# M5_Camera.net
KiCad netlist of a schematic drawn in Altium Designer
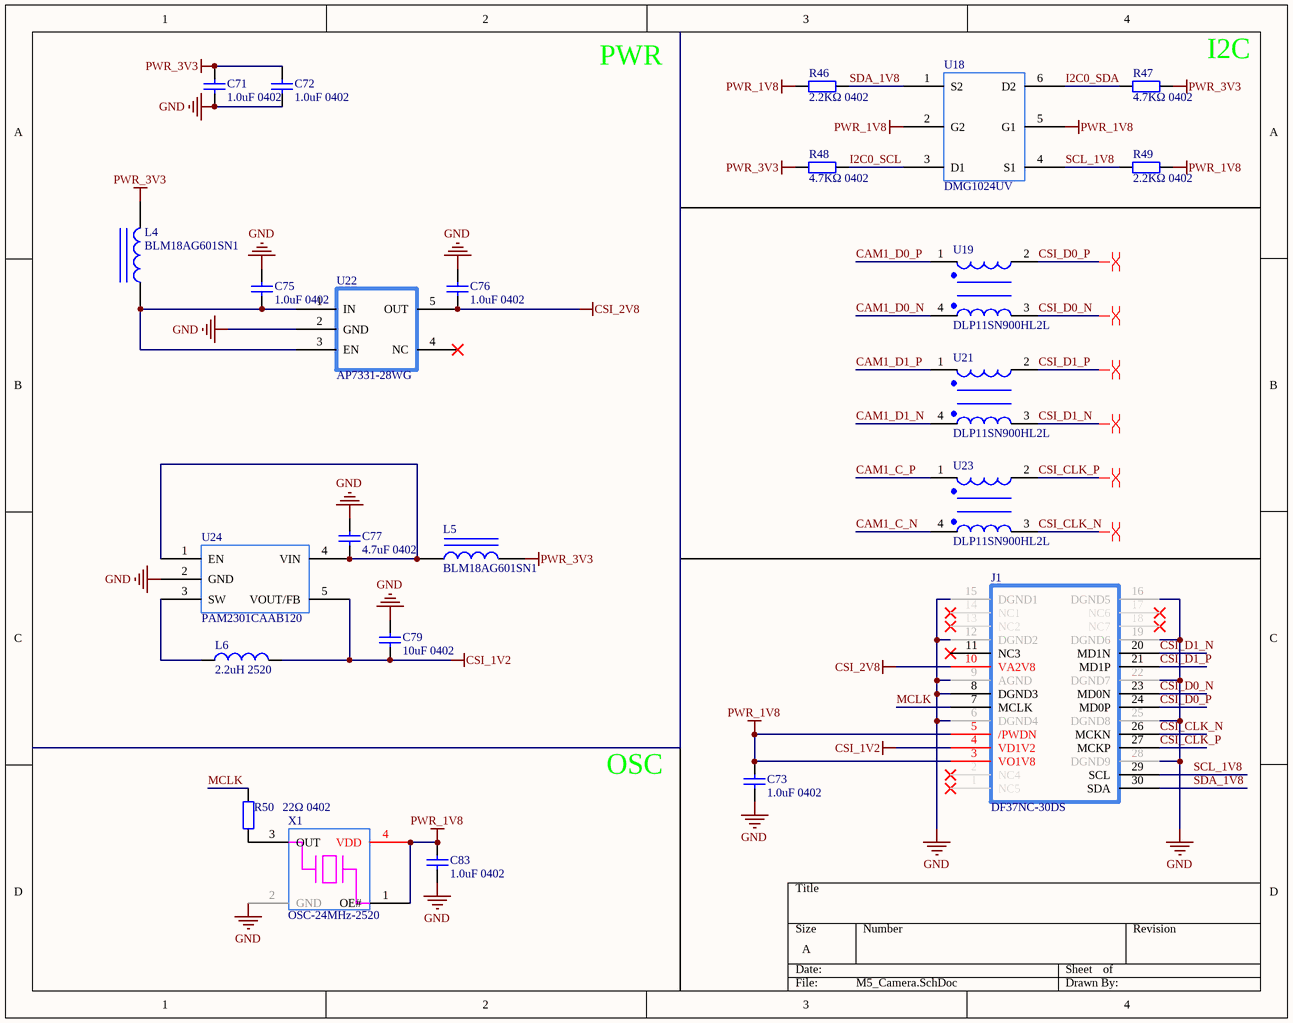
[diagram p0: M5_Camera.SchDoc]

(export (version "E")
  (design (tool "Eeschema 10.0.6"))
  (components
    (comp (ref "C71")
      (value "1.0uF 0402")
      (footprint "0402_C")
      (description "贴片电容")
      (libsource (lib "Miscellaneous Devices LC") (part "0402 1.0uF (105) 10% 25V"))
    )
    (comp (ref "C72")
      (value "1.0uF 0402")
      (footprint "0402_C")
      (description "贴片电容")
      (libsource (lib "Miscellaneous Devices LC") (part "0402 1.0uF (105) 10% 25V"))
    )
    (comp (ref "C73")
      (value "1.0uF 0402")
      (footprint "0402_C")
      (description "贴片电容")
      (libsource (lib "Miscellaneous Devices LC") (part "0402 1.0uF (105) 10% 25V"))
    )
    (comp (ref "C75")
      (value "1.0uF 0402")
      (footprint "0402_C")
      (description "贴片电容")
      (libsource (lib "Miscellaneous Devices LC") (part "0402 1.0uF (105) 10% 25V"))
    )
    (comp (ref "C76")
      (value "1.0uF 0402")
      (footprint "0402_C")
      (description "贴片电容")
      (libsource (lib "Miscellaneous Devices LC") (part "0402 1.0uF (105) 10% 25V"))
    )
    (comp (ref "C77")
      (value "4.7uF 0402")
      (footprint "0402_C")
      (description "贴片电容")
      (libsource (lib "Miscellaneous Devices LC") (part "0402 4.7uF (475) 20% 10V"))
    )
    (comp (ref "C79")
      (value "10uF 0402")
      (footprint "0402_C")
      (description "贴片电容")
      (libsource (lib "Miscellaneous Devices LC") (part "0402 10uF (106) 20% 6.3V"))
    )
    (comp (ref "C83")
      (value "1.0uF 0402")
      (footprint "0402_C")
      (description "贴片电容")
      (libsource (lib "Miscellaneous Devices LC") (part "0402 1.0uF (105) 10% 25V"))
    )
    (comp (ref "J1")
      (value "DF37NC-30DS")
      (footprint "DF37NF-30DS")
      (description "Camera Connector")
      (libsource (lib "Sensor") (part "DF37NC-30DS"))
    )
    (comp (ref "L4")
      (value "BLM18AG601SN1")
      (footprint "0603_L")
      (description "贴片电感")
      (libsource (lib "Miscellaneous Devices LC") (part "0603 10uH 10%"))
    )
    (comp (ref "L5")
      (value "BLM18AG601SN1")
      (footprint "0603_L")
      (description "贴片电感")
      (libsource (lib "Miscellaneous Devices LC") (part "0603 10uH 10%"))
    )
    (comp (ref "L6")
      (value "2.2uH 2520")
      (footprint "2.2uH 2520")
      (description "2520")
      (fields (field (name "MP") "DFE252008U-2R2M=P2"))
      (libsource (lib "Sensor") (part "2.2uH 2520"))
    )
    (comp (ref "R46")
      (value "2.2KΩ 0402")
      (footprint "0402_R")
      (description "贴片电阻")
      (libsource (lib "Miscellaneous Devices LC") (part "0402 2.2KΩ (2201) 1%"))
    )
    (comp (ref "R47")
      (value "4.7KΩ 0402")
      (footprint "0402_R")
      (description "贴片电阻")
      (libsource (lib "Miscellaneous Devices LC") (part "0402 4.7KΩ (4701) 1%"))
    )
    (comp (ref "R48")
      (value "4.7KΩ 0402")
      (footprint "0402_R")
      (description "贴片电阻")
      (libsource (lib "Miscellaneous Devices LC") (part "0402 4.7KΩ (4701) 1%"))
    )
    (comp (ref "R49")
      (value "2.2KΩ 0402")
      (footprint "0402_R")
      (description "贴片电阻")
      (libsource (lib "Miscellaneous Devices LC") (part "0402 2.2KΩ (2201) 1%"))
    )
    (comp (ref "R50")
      (value "22Ω 0402")
      (footprint "0402_R")
      (description "贴片电阻")
      (libsource (lib "Miscellaneous Devices LC") (part "0402 22Ω (22R0) 1%"))
    )
    (comp (ref "U18")
      (value "DMG1024UV")
      (footprint "DMG1024UV")
      (description "Camera")
      (libsource (lib "Sensor") (part "DMG1024UV"))
    )
    (comp (ref "U19")
      (value "DLP11SN900HL2L")
      (footprint "DLP11SN900HL2L")
      (description "Camera")
      (libsource (lib "Sensor") (part "DLP11SN900HL2L"))
    )
    (comp (ref "U21")
      (value "DLP11SN900HL2L")
      (footprint "DLP11SN900HL2L")
      (description "Camera")
      (libsource (lib "Sensor") (part "DLP11SN900HL2L"))
    )
    (comp (ref "U22")
      (value "AP7331-28WG")
      (footprint "AP7331-28WG")
      (description "Camera 2.8V")
      (libsource (lib "Sensor") (part "AP7331-28WG"))
    )
    (comp (ref "U23")
      (value "DLP11SN900HL2L")
      (footprint "DLP11SN900HL2L")
      (description "Camera")
      (libsource (lib "Sensor") (part "DLP11SN900HL2L"))
    )
    (comp (ref "U24")
      (value "PAM2301CAAB120")
      (footprint "PAM2301CAAB120")
      (description "Camera 1.2V")
      (libsource (lib "Sensor") (part "PAM2301CAAB120"))
    )
    (comp (ref "X1")
      (value "OSC-24MHz-2520")
      (footprint "OSC-24MHz-2520")
      (description "24MHz Camera")
      (libsource (lib "Sensor") (part "OSC-24MHz-2520"))
    )
  )
  (nets
    (net (code "1") (name "/CAM1_C_N") (class "Default")
      (node (ref "U23") (pin "4") (pinfunction "4_4") (pintype "passive"))
    )
    (net (code "2") (name "/CAM1_C_P") (class "Default")
      (node (ref "U23") (pin "1") (pinfunction "1_1") (pintype "passive"))
    )
    (net (code "3") (name "/CAM1_D0_N") (class "Default")
      (node (ref "U19") (pin "4") (pinfunction "4_4") (pintype "passive"))
    )
    (net (code "4") (name "/CAM1_D0_P") (class "Default")
      (node (ref "U19") (pin "1") (pinfunction "1_1") (pintype "passive"))
    )
    (net (code "5") (name "/CAM1_D1_N") (class "Default")
      (node (ref "U21") (pin "4") (pinfunction "4_4") (pintype "passive"))
    )
    (net (code "6") (name "/CAM1_D1_P") (class "Default")
      (node (ref "U21") (pin "1") (pinfunction "1_1") (pintype "passive"))
    )
    (net (code "7") (name "/CSI_CLK_N") (class "Default")
      (node (ref "J1") (pin "26") (pinfunction "MCKN_26") (pintype "passive"))
      (node (ref "U23") (pin "3") (pinfunction "3_3") (pintype "passive"))
    )
    (net (code "8") (name "/CSI_CLK_P") (class "Default")
      (node (ref "J1") (pin "27") (pinfunction "MCKP_27") (pintype "passive"))
      (node (ref "U23") (pin "2") (pinfunction "2_2") (pintype "passive"))
    )
    (net (code "9") (name "/CSI_D0_N") (class "Default")
      (node (ref "J1") (pin "23") (pinfunction "MD0N_23") (pintype "passive"))
      (node (ref "U19") (pin "3") (pinfunction "3_3") (pintype "passive"))
    )
    (net (code "10") (name "/CSI_D0_P") (class "Default")
      (node (ref "J1") (pin "24") (pinfunction "MD0P_24") (pintype "passive"))
      (node (ref "U19") (pin "2") (pinfunction "2_2") (pintype "passive"))
    )
    (net (code "11") (name "/CSI_D1_N") (class "Default")
      (node (ref "J1") (pin "20") (pinfunction "MD1N_20") (pintype "passive"))
      (node (ref "U21") (pin "3") (pinfunction "3_3") (pintype "passive"))
    )
    (net (code "12") (name "/CSI_D1_P") (class "Default")
      (node (ref "J1") (pin "21") (pinfunction "MD1P_21") (pintype "passive"))
      (node (ref "U21") (pin "2") (pinfunction "2_2") (pintype "passive"))
    )
    (net (code "13") (name "/I2C0_SCL") (class "Default")
      (node (ref "R48") (pin "2") (pinfunction "2_2") (pintype "passive"))
      (node (ref "U18") (pin "3") (pinfunction "D1_3") (pintype "passive"))
    )
    (net (code "14") (name "/I2C0_SDA") (class "Default")
      (node (ref "R47") (pin "1") (pinfunction "1_1") (pintype "passive"))
      (node (ref "U18") (pin "6") (pinfunction "D2_6") (pintype "passive"))
    )
    (net (code "15") (name "/MCLK") (class "Default")
      (node (ref "J1") (pin "7") (pinfunction "MCLK_7") (pintype "passive"))
      (node (ref "R50") (pin "1") (pinfunction "1_1") (pintype "passive"))
    )
    (net (code "16") (name "/SCL_1V8") (class "Default")
      (node (ref "J1") (pin "29") (pinfunction "SCL_29") (pintype "passive"))
      (node (ref "R49") (pin "1") (pinfunction "1_1") (pintype "passive"))
      (node (ref "U18") (pin "4") (pinfunction "S1_4") (pintype "passive"))
    )
    (net (code "17") (name "/SDA_1V8") (class "Default")
      (node (ref "J1") (pin "30") (pinfunction "SDA_30") (pintype "passive"))
      (node (ref "R46") (pin "2") (pinfunction "2_2") (pintype "passive"))
      (node (ref "U18") (pin "1") (pinfunction "S2_1") (pintype "passive"))
    )
    (net (code "18") (name "CSI_1V2") (class "Default")
      (node (ref "C79") (pin "2") (pinfunction "2_2") (pintype "passive"))
      (node (ref "J1") (pin "4") (pinfunction "VD1V2_4") (pintype "passive"))
      (node (ref "L6") (pin "2") (pinfunction "2_2") (pintype "passive"))
      (node (ref "U24") (pin "5") (pinfunction "VOUT/FB_5") (pintype "passive"))
    )
    (net (code "19") (name "CSI_2V8") (class "Default")
      (node (ref "C76") (pin "1") (pinfunction "1_1") (pintype "passive"))
      (node (ref "J1") (pin "10") (pinfunction "VA2V8_10") (pintype "passive"))
      (node (ref "U22") (pin "5") (pinfunction "OUT_5") (pintype "passive"))
    )
    (net (code "20") (name "GND") (class "Default")
      (node (ref "C71") (pin "1") (pinfunction "1_1") (pintype "passive"))
      (node (ref "C72") (pin "1") (pinfunction "1_1") (pintype "passive"))
      (node (ref "C73") (pin "1") (pinfunction "1_1") (pintype "passive"))
      (node (ref "C75") (pin "2") (pinfunction "2_2") (pintype "passive"))
      (node (ref "C76") (pin "2") (pinfunction "2_2") (pintype "passive"))
      (node (ref "C77") (pin "2") (pinfunction "2_2") (pintype "passive"))
      (node (ref "C79") (pin "1") (pinfunction "1_1") (pintype "passive"))
      (node (ref "C83") (pin "1") (pinfunction "1_1") (pintype "passive"))
      (node (ref "J1") (pin "12") (pinfunction "DGND2_12") (pintype "passive"))
      (node (ref "J1") (pin "15") (pinfunction "DGND1_15") (pintype "passive"))
      (node (ref "J1") (pin "16") (pinfunction "DGND5_16") (pintype "passive"))
      (node (ref "J1") (pin "19") (pinfunction "DGND6_19") (pintype "passive"))
      (node (ref "J1") (pin "22") (pinfunction "DGND7_22") (pintype "passive"))
      (node (ref "J1") (pin "25") (pinfunction "DGND8_25") (pintype "passive"))
      (node (ref "J1") (pin "28") (pinfunction "DGND9_28") (pintype "passive"))
      (node (ref "J1") (pin "6") (pinfunction "DGND4_6") (pintype "passive"))
      (node (ref "J1") (pin "8") (pinfunction "DGND3_8") (pintype "passive"))
      (node (ref "J1") (pin "9") (pinfunction "AGND_9") (pintype "passive"))
      (node (ref "U22") (pin "2") (pinfunction "GND_2") (pintype "passive"))
      (node (ref "U24") (pin "2") (pinfunction "GND_2") (pintype "passive"))
      (node (ref "X1") (pin "2") (pinfunction "GND_2") (pintype "passive"))
    )
    (net (code "21") (name "Net-(U22-EN)") (class "Default")
      (node (ref "C75") (pin "1") (pinfunction "1_1") (pintype "passive"))
      (node (ref "L4") (pin "1") (pinfunction "1_1") (pintype "passive"))
      (node (ref "U22") (pin "1") (pinfunction "IN_1") (pintype "passive"))
      (node (ref "U22") (pin "3") (pinfunction "EN_3") (pintype "passive"))
    )
    (net (code "22") (name "Net-(U24-EN)") (class "Default")
      (node (ref "C77") (pin "1") (pinfunction "1_1") (pintype "passive"))
      (node (ref "L5") (pin "1") (pinfunction "1_1") (pintype "passive"))
      (node (ref "U24") (pin "1") (pinfunction "EN_1") (pintype "passive"))
      (node (ref "U24") (pin "4") (pinfunction "VIN_4") (pintype "passive"))
    )
    (net (code "23") (name "Net-(U24-SW)") (class "Default")
      (node (ref "L6") (pin "1") (pinfunction "1_1") (pintype "passive"))
      (node (ref "U24") (pin "3") (pinfunction "SW_3") (pintype "passive"))
    )
    (net (code "24") (name "Net-(X1-OUT)") (class "Default")
      (node (ref "R50") (pin "2") (pinfunction "2_2") (pintype "passive"))
      (node (ref "X1") (pin "3") (pinfunction "OUT_3") (pintype "passive"))
    )
    (net (code "25") (name "PWR_1V8") (class "Default")
      (node (ref "C73") (pin "2") (pinfunction "2_2") (pintype "passive"))
      (node (ref "C83") (pin "2") (pinfunction "2_2") (pintype "passive"))
      (node (ref "J1") (pin "3") (pinfunction "VO1V8_3") (pintype "passive"))
      (node (ref "J1") (pin "5") (pinfunction "/PWDN_5") (pintype "passive"))
      (node (ref "R46") (pin "1") (pinfunction "1_1") (pintype "passive"))
      (node (ref "R49") (pin "2") (pinfunction "2_2") (pintype "passive"))
      (node (ref "U18") (pin "2") (pinfunction "G2_2") (pintype "passive"))
      (node (ref "U18") (pin "5") (pinfunction "G1_5") (pintype "passive"))
      (node (ref "X1") (pin "1") (pinfunction "OE#_1") (pintype "passive"))
      (node (ref "X1") (pin "4") (pinfunction "VDD_4") (pintype "passive"))
    )
    (net (code "26") (name "PWR_3V3") (class "Default")
      (node (ref "C71") (pin "2") (pinfunction "2_2") (pintype "passive"))
      (node (ref "C72") (pin "2") (pinfunction "2_2") (pintype "passive"))
      (node (ref "L4") (pin "2") (pinfunction "2_2") (pintype "passive"))
      (node (ref "L5") (pin "2") (pinfunction "2_2") (pintype "passive"))
      (node (ref "R47") (pin "2") (pinfunction "2_2") (pintype "passive"))
      (node (ref "R48") (pin "1") (pinfunction "1_1") (pintype "passive"))
    )
    (net (code "27") (name "unconnected-(J1-NC1-Pad14)") (class "Default")
      (node (ref "J1") (pin "14") (pinfunction "NC1_14") (pintype "passive+no_connect"))
    )
    (net (code "28") (name "unconnected-(J1-NC2-Pad13)") (class "Default")
      (node (ref "J1") (pin "13") (pinfunction "NC2_13") (pintype "passive+no_connect"))
    )
    (net (code "29") (name "unconnected-(J1-NC3-Pad11)") (class "Default")
      (node (ref "J1") (pin "11") (pinfunction "NC3_11") (pintype "passive+no_connect"))
    )
    (net (code "30") (name "unconnected-(J1-NC4-Pad2)") (class "Default")
      (node (ref "J1") (pin "2") (pinfunction "NC4_2") (pintype "passive+no_connect"))
    )
    (net (code "31") (name "unconnected-(J1-NC5-Pad1)") (class "Default")
      (node (ref "J1") (pin "1") (pinfunction "NC5_1") (pintype "passive+no_connect"))
    )
    (net (code "32") (name "unconnected-(J1-NC6-Pad17)") (class "Default")
      (node (ref "J1") (pin "17") (pinfunction "NC6_17") (pintype "passive+no_connect"))
    )
    (net (code "33") (name "unconnected-(J1-NC7-Pad18)") (class "Default")
      (node (ref "J1") (pin "18") (pinfunction "NC7_18") (pintype "passive+no_connect"))
    )
    (net (code "34") (name "unconnected-(U22-NC-Pad4)") (class "Default")
      (node (ref "U22") (pin "4") (pinfunction "NC_4") (pintype "power_in+no_connect"))
    )
  )
)
